# Adder.net
KiCad netlist of a schematic drawn in Altium Designer
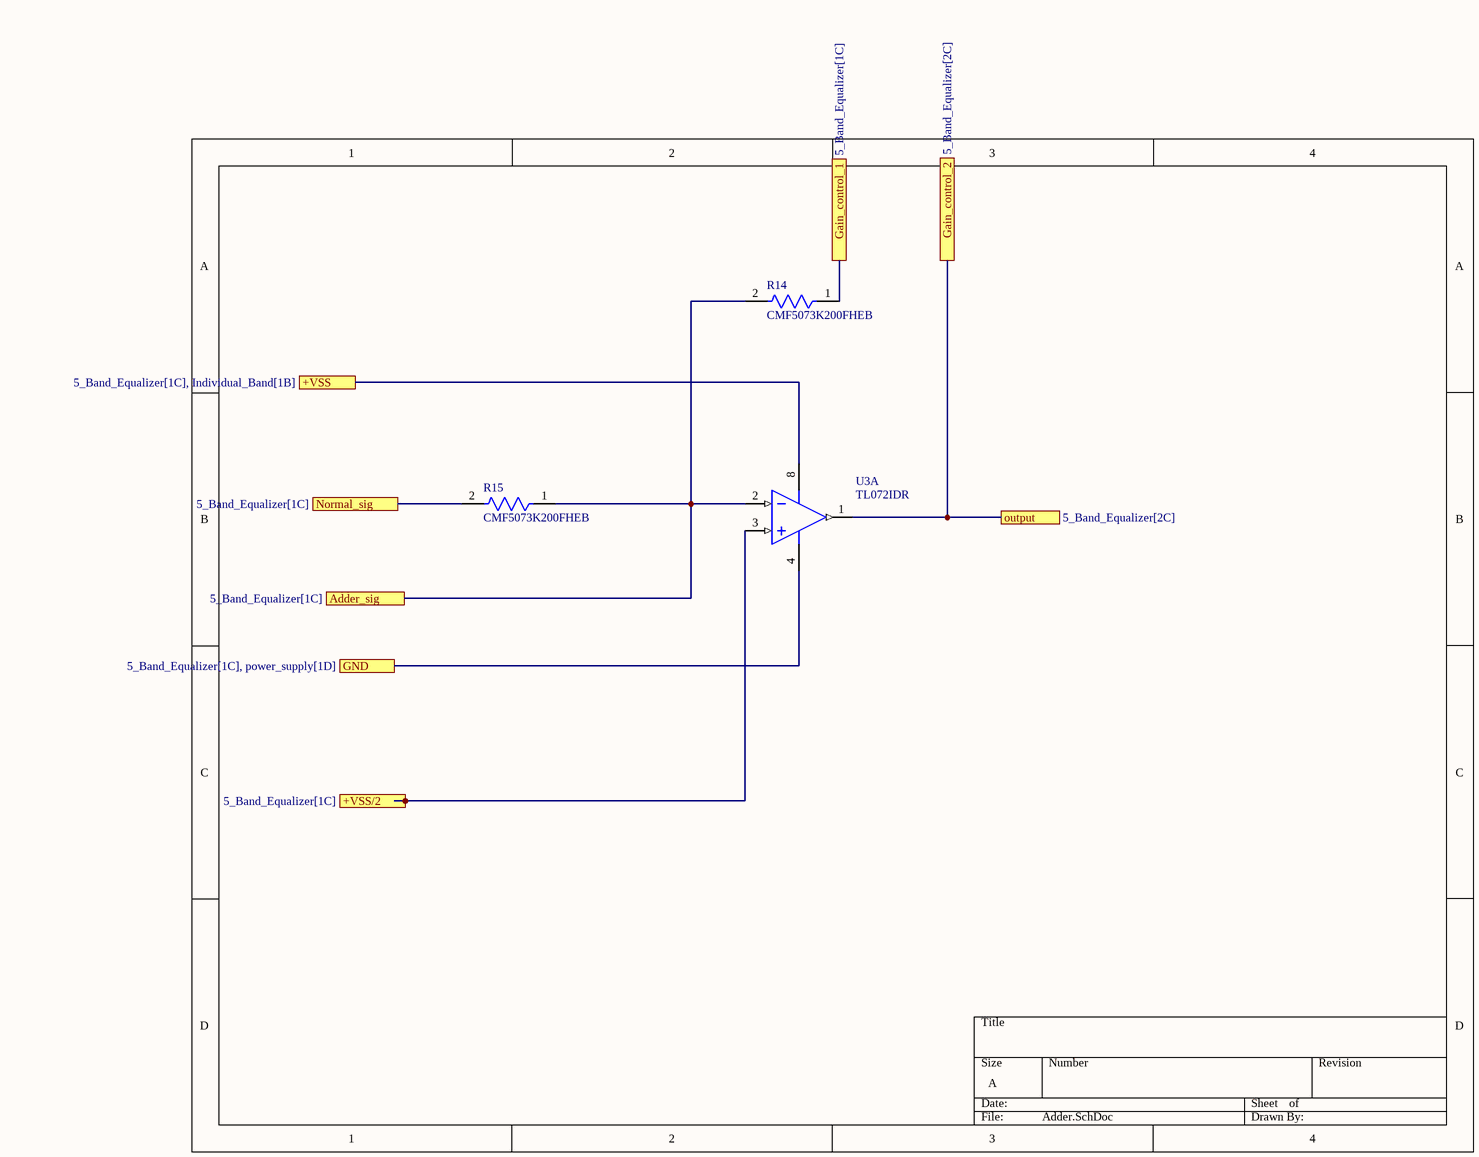
[diagram p0: Adder.SchDoc]

(export (version "E")
  (design (tool "Eeschema 10.0.6"))
  (components
    (comp (ref "R14")
      (value "CMF5073K200FHEB")
      (footprint "FP-CMF50-0")
      (description "CMF5073K200FHEB Res Metal Film 73.2K Ohm 1% 0.125W(1/8W) ±50ppm/°C Epoxy AXL T/R")
      (fields (field (name "TOLERANCE") "1%"))
      (libsource (lib "Altium Content Vault") (part "1029c3af85768c4190bb7ad29bc67b5"))
    )
    (comp (ref "R15")
      (value "CMF5073K200FHEB")
      (footprint "FP-CMF50-0")
      (description "CMF5073K200FHEB Res Metal Film 73.2K Ohm 1% 0.125W(1/8W) ±50ppm/°C Epoxy AXL T/R")
      (fields (field (name "TOLERANCE") "1%"))
      (libsource (lib "Altium Content Vault") (part "1029c3af85768c4190bb7ad29bc67b5"))
    )
    (comp (ref "U3")
      (value "TL072IDR")
      (footprint "D0008A_L")
      (fields (field (name "MANUFACTURER") "Texas Instruments"))
      (libsource (lib "Altium Content Vault") (part "TI-AMP-D6-2-8_D"))
    )
  )
  (nets
    (net (code "1") (name "/+VSS") (class "Default")
      (node (ref "U3") (pin "8") (pinfunction "VCC+_8") (pintype "power_in"))
    )
    (net (code "2") (name "/+VSS{slash}2") (class "Default")
      (node (ref "U3") (pin "3") (pinfunction "IN1+_3") (pintype "input"))
    )
    (net (code "3") (name "/Adder_sig") (class "Default")
      (node (ref "R14") (pin "2") (pinfunction "2_2") (pintype "passive"))
      (node (ref "R15") (pin "1") (pinfunction "1_1") (pintype "passive"))
      (node (ref "U3") (pin "2") (pinfunction "IN1-_2") (pintype "input"))
    )
    (net (code "4") (name "/GND") (class "Default")
      (node (ref "U3") (pin "4") (pinfunction "VCC-_4") (pintype "power_in"))
    )
    (net (code "5") (name "/Gain_control_1") (class "Default")
      (node (ref "R14") (pin "1") (pinfunction "1_1") (pintype "passive"))
    )
    (net (code "6") (name "/Gain_control_2") (class "Default")
      (node (ref "U3") (pin "1") (pinfunction "OUT1_1") (pintype "output"))
    )
    (net (code "7") (name "/Normal_sig") (class "Default")
      (node (ref "R15") (pin "2") (pinfunction "2_2") (pintype "passive"))
    )
  )
)
